# LoRa-Bootsmonitor_3_1.net
KiCad netlist of a schematic drawn in EAGLE
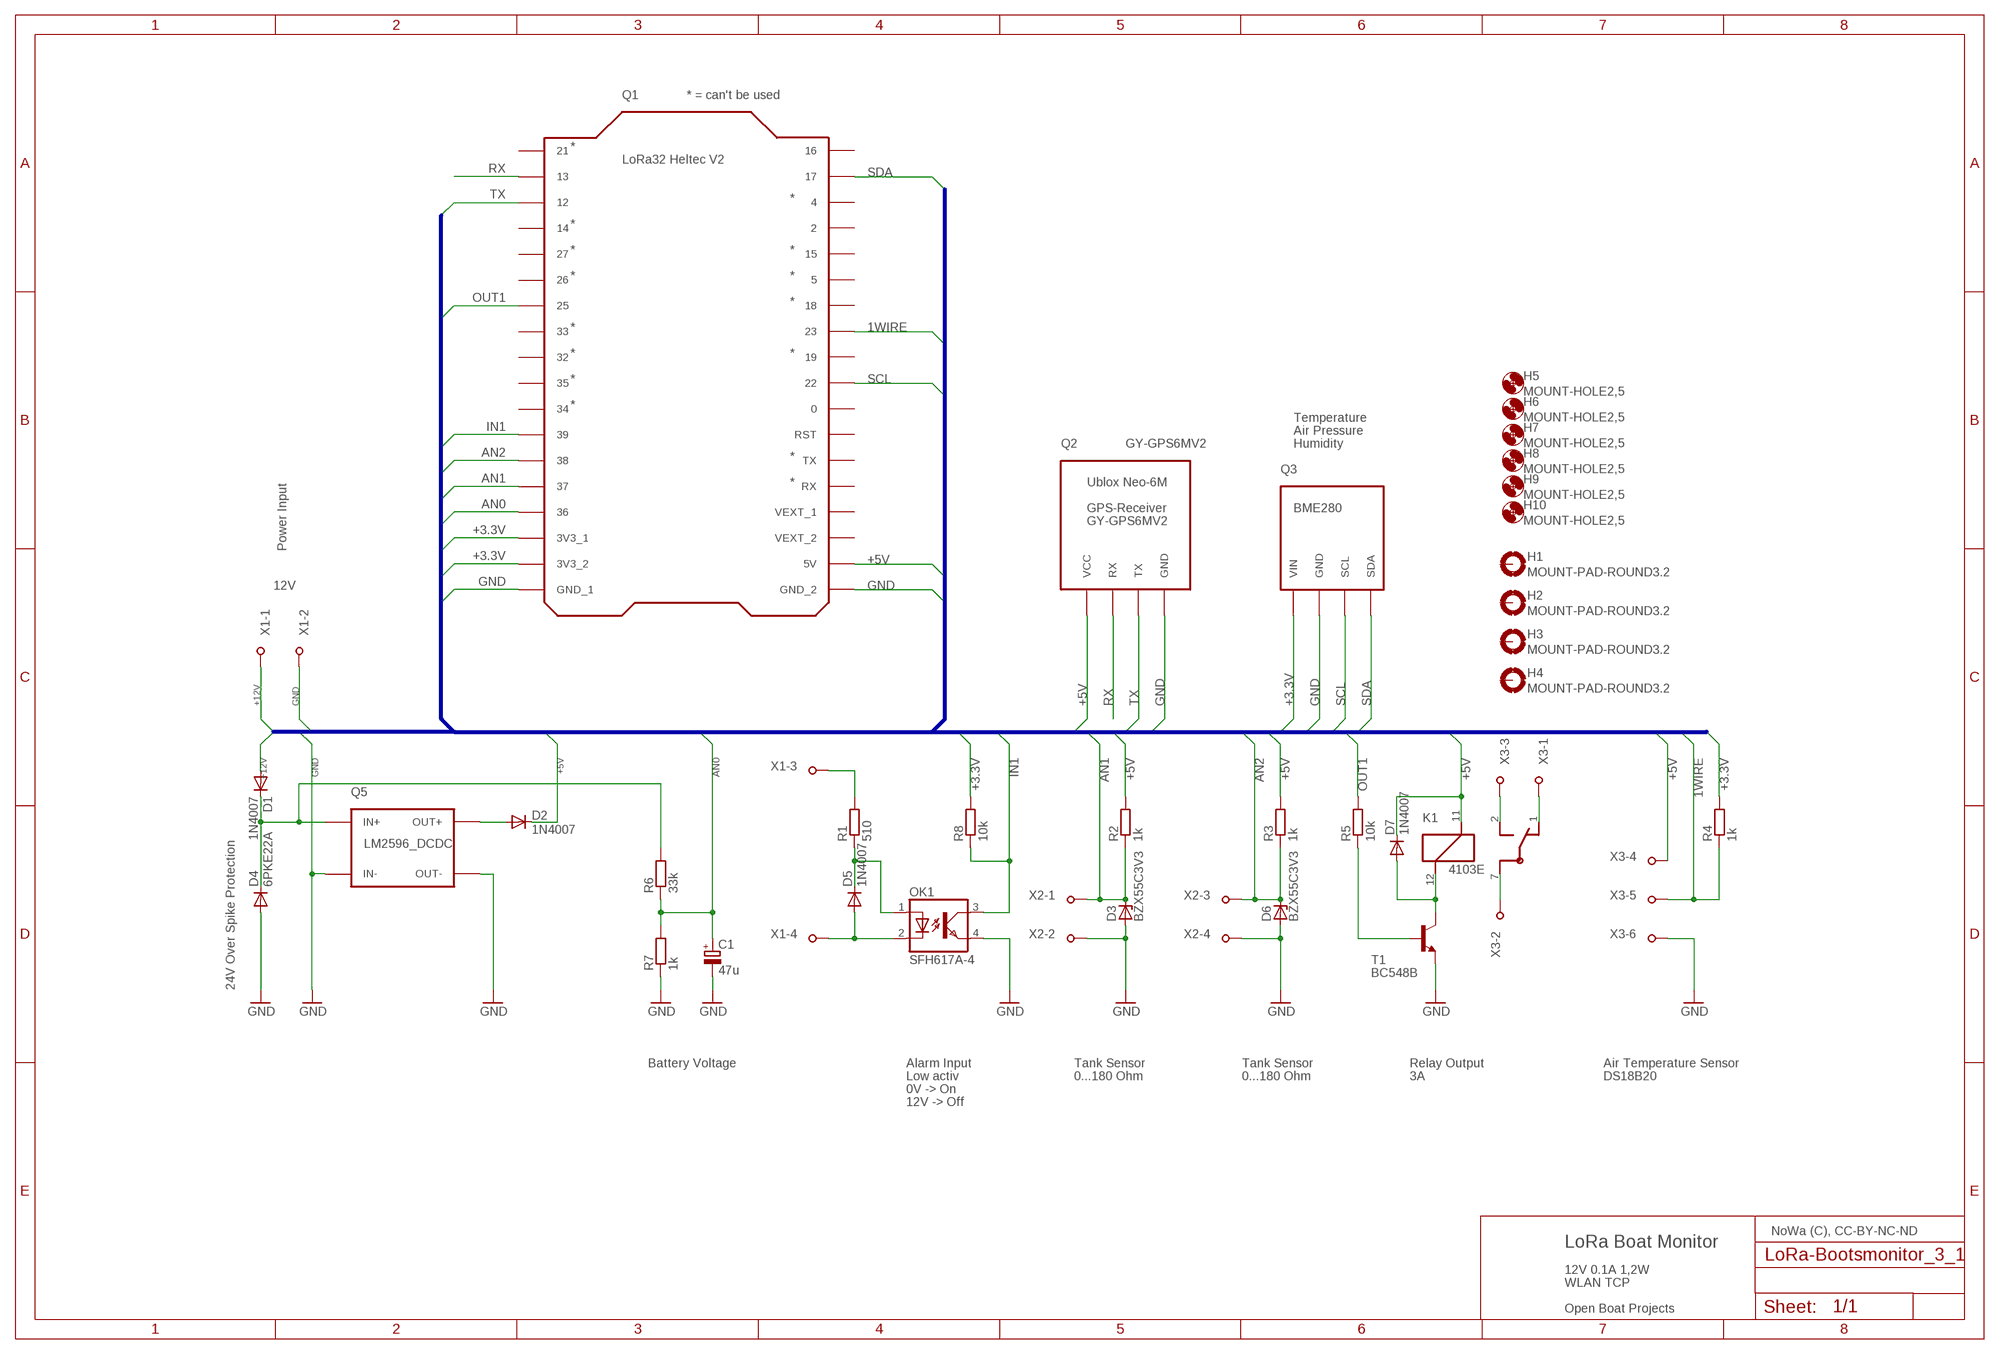
[diagram p0: schematic, sheet 1]

(export (version "E")
  (design (tool "Eeschema 10.0.6"))
  (components
    (comp (ref "C1")
      (value "47u")
      (footprint "eagle-import:E3,5-8")
      (libsource (lib "eagle-import") (part "CPOL-EUE3.5-8"))
    )
    (comp (ref "D1")
      (value "1N4007")
      (footprint "eagle-import:SOD81")
      (libsource (lib "eagle-import") (part "BYD13"))
    )
    (comp (ref "D2")
      (value "1N4007")
      (footprint "eagle-import:SOD81")
      (libsource (lib "eagle-import") (part "BYD13"))
    )
    (comp (ref "D3")
      (value "BZX55C3V3")
      (footprint "eagle-import:DO35Z10")
      (libsource (lib "eagle-import") (part "BZX55"))
    )
    (comp (ref "D4")
      (value "6PKE22A")
      (footprint "eagle-import:DO201-15")
      (libsource (lib "eagle-import") (part "1N5400"))
    )
    (comp (ref "D5")
      (value "1N4007")
      (footprint "eagle-import:SOD81")
      (libsource (lib "eagle-import") (part "BYD13"))
    )
    (comp (ref "D6")
      (value "BZX55C3V3")
      (footprint "eagle-import:DO35Z10")
      (libsource (lib "eagle-import") (part "BZX55"))
    )
    (comp (ref "D7")
      (value "1N4007")
      (footprint "eagle-import:SOD81")
      (libsource (lib "eagle-import") (part "BYD13"))
    )
    (comp (ref "H1")
      (value "MOUNT-PAD-ROUND3.2")
      (footprint "eagle-import:3,2-PAD")
      (libsource (lib "eagle-import") (part "MOUNT-PAD-ROUND3.2"))
    )
    (comp (ref "H2")
      (value "MOUNT-PAD-ROUND3.2")
      (footprint "eagle-import:3,2-PAD")
      (libsource (lib "eagle-import") (part "MOUNT-PAD-ROUND3.2"))
    )
    (comp (ref "H3")
      (value "MOUNT-PAD-ROUND3.2")
      (footprint "eagle-import:3,2-PAD")
      (libsource (lib "eagle-import") (part "MOUNT-PAD-ROUND3.2"))
    )
    (comp (ref "H4")
      (value "MOUNT-PAD-ROUND3.2")
      (footprint "eagle-import:3,2-PAD")
      (libsource (lib "eagle-import") (part "MOUNT-PAD-ROUND3.2"))
    )
    (comp (ref "H5")
      (value "MOUNT-HOLE2,5")
      (footprint "eagle-import:2,5")
      (libsource (lib "eagle-import") (part "MOUNT-HOLE2,5"))
    )
    (comp (ref "H6")
      (value "MOUNT-HOLE2,5")
      (footprint "eagle-import:2,5")
      (libsource (lib "eagle-import") (part "MOUNT-HOLE2,5"))
    )
    (comp (ref "H7")
      (value "MOUNT-HOLE2,5")
      (footprint "eagle-import:2,5")
      (libsource (lib "eagle-import") (part "MOUNT-HOLE2,5"))
    )
    (comp (ref "H8")
      (value "MOUNT-HOLE2,5")
      (footprint "eagle-import:2,5")
      (libsource (lib "eagle-import") (part "MOUNT-HOLE2,5"))
    )
    (comp (ref "H9")
      (value "MOUNT-HOLE2,5")
      (footprint "eagle-import:2,5")
      (libsource (lib "eagle-import") (part "MOUNT-HOLE2,5"))
    )
    (comp (ref "H10")
      (value "MOUNT-HOLE2,5")
      (footprint "eagle-import:2,5")
      (libsource (lib "eagle-import") (part "MOUNT-HOLE2,5"))
    )
    (comp (ref "K1")
      (value "4103E")
      (footprint "eagle-import:RELAIS_4102E")
      (libsource (lib "eagle-import") (part "RELAIS_4102E"))
    )
    (comp (ref "OK1")
      (value "SFH617A-4")
      (footprint "eagle-import:DIL04")
      (libsource (lib "eagle-import") (part "SFH610"))
    )
    (comp (ref "Q1")
      (value "LORA32_HELTEC_V2")
      (footprint "eagle-import:LORA32_HELTEC_V2")
      (libsource (lib "eagle-import") (part "LORA32_HELTEC_V2"))
    )
    (comp (ref "Q2")
      (value "GY-GPS6MV2")
      (footprint "eagle-import:GY_GPS6MV2_H")
      (libsource (lib "eagle-import") (part "GY_GPS6MV2_H"))
    )
    (comp (ref "Q3")
      (value "BME280")
      (footprint "eagle-import:BME280")
      (libsource (lib "eagle-import") (part "BME280"))
    )
    (comp (ref "Q5")
      (value "LM2596_DCDC")
      (footprint "eagle-import:LM2596_DCDC")
      (libsource (lib "eagle-import") (part "LM2596_DCDC"))
    )
    (comp (ref "R1")
      (value "510")
      (footprint "eagle-import:0207_10")
      (libsource (lib "eagle-import") (part "R-EU_0207/10"))
    )
    (comp (ref "R2")
      (value "1k")
      (footprint "eagle-import:0207_10")
      (libsource (lib "eagle-import") (part "R-EU_0207/10"))
    )
    (comp (ref "R3")
      (value "1k")
      (footprint "eagle-import:0207_10")
      (libsource (lib "eagle-import") (part "R-EU_0207/10"))
    )
    (comp (ref "R4")
      (value "1k")
      (footprint "eagle-import:0207_10")
      (libsource (lib "eagle-import") (part "R-EU_0207/10"))
    )
    (comp (ref "R5")
      (value "10k")
      (footprint "eagle-import:0207_10")
      (libsource (lib "eagle-import") (part "R-EU_0207/10"))
    )
    (comp (ref "R6")
      (value "33k")
      (footprint "eagle-import:0207_10")
      (libsource (lib "eagle-import") (part "R-EU_0207/10"))
    )
    (comp (ref "R7")
      (value "1k")
      (footprint "eagle-import:0207_10")
      (libsource (lib "eagle-import") (part "R-EU_0207/10"))
    )
    (comp (ref "R8")
      (value "10k")
      (footprint "eagle-import:0207_10")
      (libsource (lib "eagle-import") (part "R-EU_0207/10"))
    )
    (comp (ref "T1")
      (value "BC548B")
      (footprint "eagle-import:TO92-EBC")
      (libsource (lib "eagle-import") (part "BC548B"))
    )
    (comp (ref "X1")
      (value "AKL_092_04")
      (footprint "eagle-import:AKL_092_04")
      (libsource (lib "eagle-import") (part "AKL_092_04"))
    )
    (comp (ref "X2")
      (value "AKL_092_04")
      (footprint "eagle-import:AKL_092_04")
      (libsource (lib "eagle-import") (part "AKL_092_04"))
    )
    (comp (ref "X3")
      (value "AKL_092_06")
      (footprint "eagle-import:AKL_092_06")
      (libsource (lib "eagle-import") (part "AKL_092_06"))
    )
  )
  (nets
    (net (code "1") (name "/+3.3V") (class "Default")
      (node (ref "Q1") (pin "34") (pinfunction "3V3_1_34") (pintype "bidirectional"))
      (node (ref "Q1") (pin "35") (pinfunction "3V3_2_35") (pintype "bidirectional"))
      (node (ref "Q3") (pin "VIN") (pinfunction "VIN_VIN") (pintype "bidirectional"))
      (node (ref "R4") (pin "2") (pinfunction "2_2") (pintype "passive"))
      (node (ref "R8") (pin "2") (pinfunction "2_2") (pintype "passive"))
    )
    (net (code "2") (name "/+5V") (class "Default")
      (node (ref "D2") (pin "C") (pinfunction "C_C") (pintype "passive"))
      (node (ref "D7") (pin "C") (pinfunction "C_C") (pintype "passive"))
      (node (ref "K1") (pin "11") (pinfunction "11_11") (pintype "bidirectional"))
      (node (ref "Q1") (pin "2") (pinfunction "5V_2") (pintype "bidirectional"))
      (node (ref "Q2") (pin "VCC") (pinfunction "VCC_VCC") (pintype "bidirectional"))
      (node (ref "R2") (pin "2") (pinfunction "2_2") (pintype "passive"))
      (node (ref "R3") (pin "2") (pinfunction "2_2") (pintype "passive"))
      (node (ref "X3") (pin "4") (pinfunction "P$1_4") (pintype "bidirectional"))
    )
    (net (code "3") (name "/+12V") (class "Default")
      (node (ref "D1") (pin "A") (pinfunction "A_A") (pintype "passive"))
      (node (ref "X1") (pin "1") (pinfunction "P$1_1") (pintype "bidirectional"))
    )
    (net (code "4") (name "/1WIRE") (class "Default")
      (node (ref "Q1") (pin "11") (pinfunction "23_11") (pintype "bidirectional"))
      (node (ref "R4") (pin "1") (pinfunction "1_1") (pintype "passive"))
      (node (ref "X3") (pin "5") (pinfunction "P$1_5") (pintype "bidirectional"))
    )
    (net (code "5") (name "/AN0") (class "Default")
      (node (ref "C1") (pin "+") (pinfunction "+_+") (pintype "passive"))
      (node (ref "Q1") (pin "33") (pinfunction "36_33") (pintype "bidirectional"))
      (node (ref "R6") (pin "1") (pinfunction "1_1") (pintype "passive"))
      (node (ref "R7") (pin "2") (pinfunction "2_2") (pintype "passive"))
    )
    (net (code "6") (name "/AN1") (class "Default")
      (node (ref "D3") (pin "C") (pinfunction "C_C") (pintype "passive"))
      (node (ref "Q1") (pin "32") (pinfunction "37_32") (pintype "bidirectional"))
      (node (ref "R2") (pin "1") (pinfunction "1_1") (pintype "passive"))
      (node (ref "X2") (pin "1") (pinfunction "P$1_1") (pintype "bidirectional"))
    )
    (net (code "7") (name "/AN2") (class "Default")
      (node (ref "D6") (pin "C") (pinfunction "C_C") (pintype "passive"))
      (node (ref "Q1") (pin "31") (pinfunction "38_31") (pintype "bidirectional"))
      (node (ref "R3") (pin "1") (pinfunction "1_1") (pintype "passive"))
      (node (ref "X2") (pin "3") (pinfunction "P$1_3") (pintype "bidirectional"))
    )
    (net (code "8") (name "/IN1") (class "Default")
      (node (ref "OK1") (pin "3") (pinfunction "COL_3") (pintype "passive"))
      (node (ref "Q1") (pin "30") (pinfunction "39_30") (pintype "bidirectional"))
      (node (ref "R8") (pin "1") (pinfunction "1_1") (pintype "passive"))
    )
    (net (code "9") (name "/OUT1") (class "Default")
      (node (ref "Q1") (pin "25") (pinfunction "25_25") (pintype "bidirectional"))
      (node (ref "R5") (pin "2") (pinfunction "2_2") (pintype "passive"))
    )
    (net (code "10") (name "/RX") (class "Default")
      (node (ref "Q1") (pin "20") (pinfunction "13_20") (pintype "bidirectional"))
      (node (ref "Q2") (pin "RX") (pinfunction "RX_RX") (pintype "bidirectional"))
    )
    (net (code "11") (name "/SCL") (class "Default")
      (node (ref "Q1") (pin "9") (pinfunction "22_9") (pintype "bidirectional"))
      (node (ref "Q3") (pin "SCL") (pinfunction "SCL_SCL") (pintype "bidirectional"))
    )
    (net (code "12") (name "/SDA") (class "Default")
      (node (ref "Q1") (pin "17") (pinfunction "17_17") (pintype "bidirectional"))
      (node (ref "Q3") (pin "SDA") (pinfunction "SDA_SDA") (pintype "bidirectional"))
    )
    (net (code "13") (name "/TX") (class "Default")
      (node (ref "Q1") (pin "21") (pinfunction "12_21") (pintype "bidirectional"))
      (node (ref "Q2") (pin "TX") (pinfunction "TX_TX") (pintype "bidirectional"))
    )
    (net (code "14") (name "GND") (class "Default")
      (node (ref "C1") (pin "-") (pinfunction "-_-") (pintype "passive"))
      (node (ref "D3") (pin "A") (pinfunction "A_A") (pintype "passive"))
      (node (ref "D4") (pin "A") (pinfunction "A_A") (pintype "passive"))
      (node (ref "D6") (pin "A") (pinfunction "A_A") (pintype "passive"))
      (node (ref "OK1") (pin "4") (pinfunction "EMIT_4") (pintype "passive"))
      (node (ref "Q1") (pin "1") (pinfunction "GND_2_1") (pintype "bidirectional"))
      (node (ref "Q1") (pin "36") (pinfunction "GND_1_36") (pintype "bidirectional"))
      (node (ref "Q2") (pin "GND") (pinfunction "GND_GND") (pintype "bidirectional"))
      (node (ref "Q3") (pin "GND") (pinfunction "GND_GND") (pintype "bidirectional"))
      (node (ref "Q5") (pin "IN-") (pinfunction "IN-_IN-") (pintype "bidirectional"))
      (node (ref "Q5") (pin "OUT-") (pinfunction "OUT-_OUT-") (pintype "bidirectional"))
      (node (ref "R7") (pin "1") (pinfunction "1_1") (pintype "passive"))
      (node (ref "T1") (pin "E") (pinfunction "E_E") (pintype "passive"))
      (node (ref "X1") (pin "2") (pinfunction "P$1_2") (pintype "bidirectional"))
      (node (ref "X2") (pin "2") (pinfunction "P$1_2") (pintype "bidirectional"))
      (node (ref "X2") (pin "4") (pinfunction "P$1_4") (pintype "bidirectional"))
      (node (ref "X3") (pin "6") (pinfunction "P$1_6") (pintype "bidirectional"))
    )
    (net (code "15") (name "Net-(D1-PadC)") (class "Default")
      (node (ref "D1") (pin "C") (pinfunction "C_C") (pintype "passive"))
      (node (ref "D4") (pin "C") (pinfunction "C_C") (pintype "passive"))
      (node (ref "Q5") (pin "IN+") (pinfunction "IN+_IN+") (pintype "bidirectional"))
      (node (ref "R6") (pin "2") (pinfunction "2_2") (pintype "passive"))
    )
    (net (code "16") (name "Net-(D2-PadA)") (class "Default")
      (node (ref "D2") (pin "A") (pinfunction "A_A") (pintype "passive"))
      (node (ref "Q5") (pin "OUT+") (pinfunction "OUT+_OUT+") (pintype "bidirectional"))
    )
    (net (code "17") (name "Net-(D7-PadA)") (class "Default")
      (node (ref "D7") (pin "A") (pinfunction "A_A") (pintype "passive"))
      (node (ref "K1") (pin "12") (pinfunction "12_12") (pintype "bidirectional"))
      (node (ref "T1") (pin "C") (pinfunction "C_C") (pintype "passive"))
    )
    (net (code "18") (name "Net-(OK1-A)") (class "Default")
      (node (ref "D5") (pin "C") (pinfunction "C_C") (pintype "passive"))
      (node (ref "OK1") (pin "1") (pinfunction "A_1") (pintype "passive"))
      (node (ref "R1") (pin "1") (pinfunction "1_1") (pintype "passive"))
    )
    (net (code "19") (name "Net-(OK1-C)") (class "Default")
      (node (ref "D5") (pin "A") (pinfunction "A_A") (pintype "passive"))
      (node (ref "OK1") (pin "2") (pinfunction "C_2") (pintype "passive"))
      (node (ref "X1") (pin "4") (pinfunction "P$1_4") (pintype "bidirectional"))
    )
    (net (code "20") (name "Net-(R5-Pad1)") (class "Default")
      (node (ref "R5") (pin "1") (pinfunction "1_1") (pintype "passive"))
      (node (ref "T1") (pin "B") (pinfunction "B_B") (pintype "passive"))
    )
    (net (code "21") (name "Net-(X1C-P$1)") (class "Default")
      (node (ref "R1") (pin "2") (pinfunction "2_2") (pintype "passive"))
      (node (ref "X1") (pin "3") (pinfunction "P$1_3") (pintype "bidirectional"))
    )
    (net (code "22") (name "Net-(X3A-P$1)") (class "Default")
      (node (ref "K1") (pin "1") (pinfunction "1_1") (pintype "bidirectional"))
      (node (ref "X3") (pin "1") (pinfunction "P$1_1") (pintype "bidirectional"))
    )
    (net (code "23") (name "Net-(X3B-P$1)") (class "Default")
      (node (ref "K1") (pin "7") (pinfunction "7_7") (pintype "bidirectional"))
      (node (ref "X3") (pin "2") (pinfunction "P$1_2") (pintype "bidirectional"))
    )
    (net (code "24") (name "Net-(X3C-P$1)") (class "Default")
      (node (ref "K1") (pin "2") (pinfunction "2_2") (pintype "bidirectional"))
      (node (ref "X3") (pin "3") (pinfunction "P$1_3") (pintype "bidirectional"))
    )
    (net (code "25") (name "unconnected-(H1-MOUNT-PadB3,2)") (class "Default")
      (node (ref "H1") (pin "B3,2") (pinfunction "MOUNT_B3,2") (pintype "passive"))
    )
    (net (code "26") (name "unconnected-(H2-MOUNT-PadB3,2)") (class "Default")
      (node (ref "H2") (pin "B3,2") (pinfunction "MOUNT_B3,2") (pintype "passive"))
    )
    (net (code "27") (name "unconnected-(H3-MOUNT-PadB3,2)") (class "Default")
      (node (ref "H3") (pin "B3,2") (pinfunction "MOUNT_B3,2") (pintype "passive"))
    )
    (net (code "28") (name "unconnected-(H4-MOUNT-PadB3,2)") (class "Default")
      (node (ref "H4") (pin "B3,2") (pinfunction "MOUNT_B3,2") (pintype "passive"))
    )
    (net (code "29") (name "unconnected-(Q1-0-Pad8)") (class "Default")
      (node (ref "Q1") (pin "8") (pinfunction "0_8") (pintype "bidirectional"))
    )
    (net (code "30") (name "unconnected-(Q1-2-Pad15)") (class "Default")
      (node (ref "Q1") (pin "15") (pinfunction "2_15") (pintype "bidirectional"))
    )
    (net (code "31") (name "unconnected-(Q1-4-Pad16)") (class "Default")
      (node (ref "Q1") (pin "16") (pinfunction "4_16") (pintype "bidirectional"))
    )
    (net (code "32") (name "unconnected-(Q1-5-Pad13)") (class "Default")
      (node (ref "Q1") (pin "13") (pinfunction "5_13") (pintype "bidirectional"))
    )
    (net (code "33") (name "unconnected-(Q1-14-Pad22)") (class "Default")
      (node (ref "Q1") (pin "22") (pinfunction "14_22") (pintype "bidirectional"))
    )
    (net (code "34") (name "unconnected-(Q1-15-Pad14)") (class "Default")
      (node (ref "Q1") (pin "14") (pinfunction "15_14") (pintype "bidirectional"))
    )
    (net (code "35") (name "unconnected-(Q1-16-Pad18)") (class "Default")
      (node (ref "Q1") (pin "18") (pinfunction "16_18") (pintype "bidirectional"))
    )
    (net (code "36") (name "unconnected-(Q1-18-Pad12)") (class "Default")
      (node (ref "Q1") (pin "12") (pinfunction "18_12") (pintype "bidirectional"))
    )
    (net (code "37") (name "unconnected-(Q1-19-Pad10)") (class "Default")
      (node (ref "Q1") (pin "10") (pinfunction "19_10") (pintype "bidirectional"))
    )
    (net (code "38") (name "unconnected-(Q1-21-Pad19)") (class "Default")
      (node (ref "Q1") (pin "19") (pinfunction "21_19") (pintype "bidirectional"))
    )
    (net (code "39") (name "unconnected-(Q1-26-Pad24)") (class "Default")
      (node (ref "Q1") (pin "24") (pinfunction "26_24") (pintype "bidirectional"))
    )
    (net (code "40") (name "unconnected-(Q1-27-Pad23)") (class "Default")
      (node (ref "Q1") (pin "23") (pinfunction "27_23") (pintype "bidirectional"))
    )
    (net (code "41") (name "unconnected-(Q1-32-Pad27)") (class "Default")
      (node (ref "Q1") (pin "27") (pinfunction "32_27") (pintype "bidirectional"))
    )
    (net (code "42") (name "unconnected-(Q1-33-Pad26)") (class "Default")
      (node (ref "Q1") (pin "26") (pinfunction "33_26") (pintype "bidirectional"))
    )
    (net (code "43") (name "unconnected-(Q1-34-Pad29)") (class "Default")
      (node (ref "Q1") (pin "29") (pinfunction "34_29") (pintype "bidirectional"))
    )
    (net (code "44") (name "unconnected-(Q1-35-Pad28)") (class "Default")
      (node (ref "Q1") (pin "28") (pinfunction "35_28") (pintype "bidirectional"))
    )
    (net (code "45") (name "unconnected-(Q1-RST-Pad7)") (class "Default")
      (node (ref "Q1") (pin "7") (pinfunction "RST_7") (pintype "bidirectional"))
    )
    (net (code "46") (name "unconnected-(Q1-RX-Pad5)") (class "Default")
      (node (ref "Q1") (pin "5") (pinfunction "RX_5") (pintype "bidirectional"))
    )
    (net (code "47") (name "unconnected-(Q1-TX-Pad6)") (class "Default")
      (node (ref "Q1") (pin "6") (pinfunction "TX_6") (pintype "bidirectional"))
    )
    (net (code "48") (name "unconnected-(Q1-VEXT_1-Pad4)") (class "Default")
      (node (ref "Q1") (pin "4") (pinfunction "VEXT_1_4") (pintype "bidirectional"))
    )
    (net (code "49") (name "unconnected-(Q1-VEXT_2-Pad3)") (class "Default")
      (node (ref "Q1") (pin "3") (pinfunction "VEXT_2_3") (pintype "bidirectional"))
    )
  )
)
